# UI_BUTTON_LED.net
KiCad netlist of a schematic drawn in Altium Designer
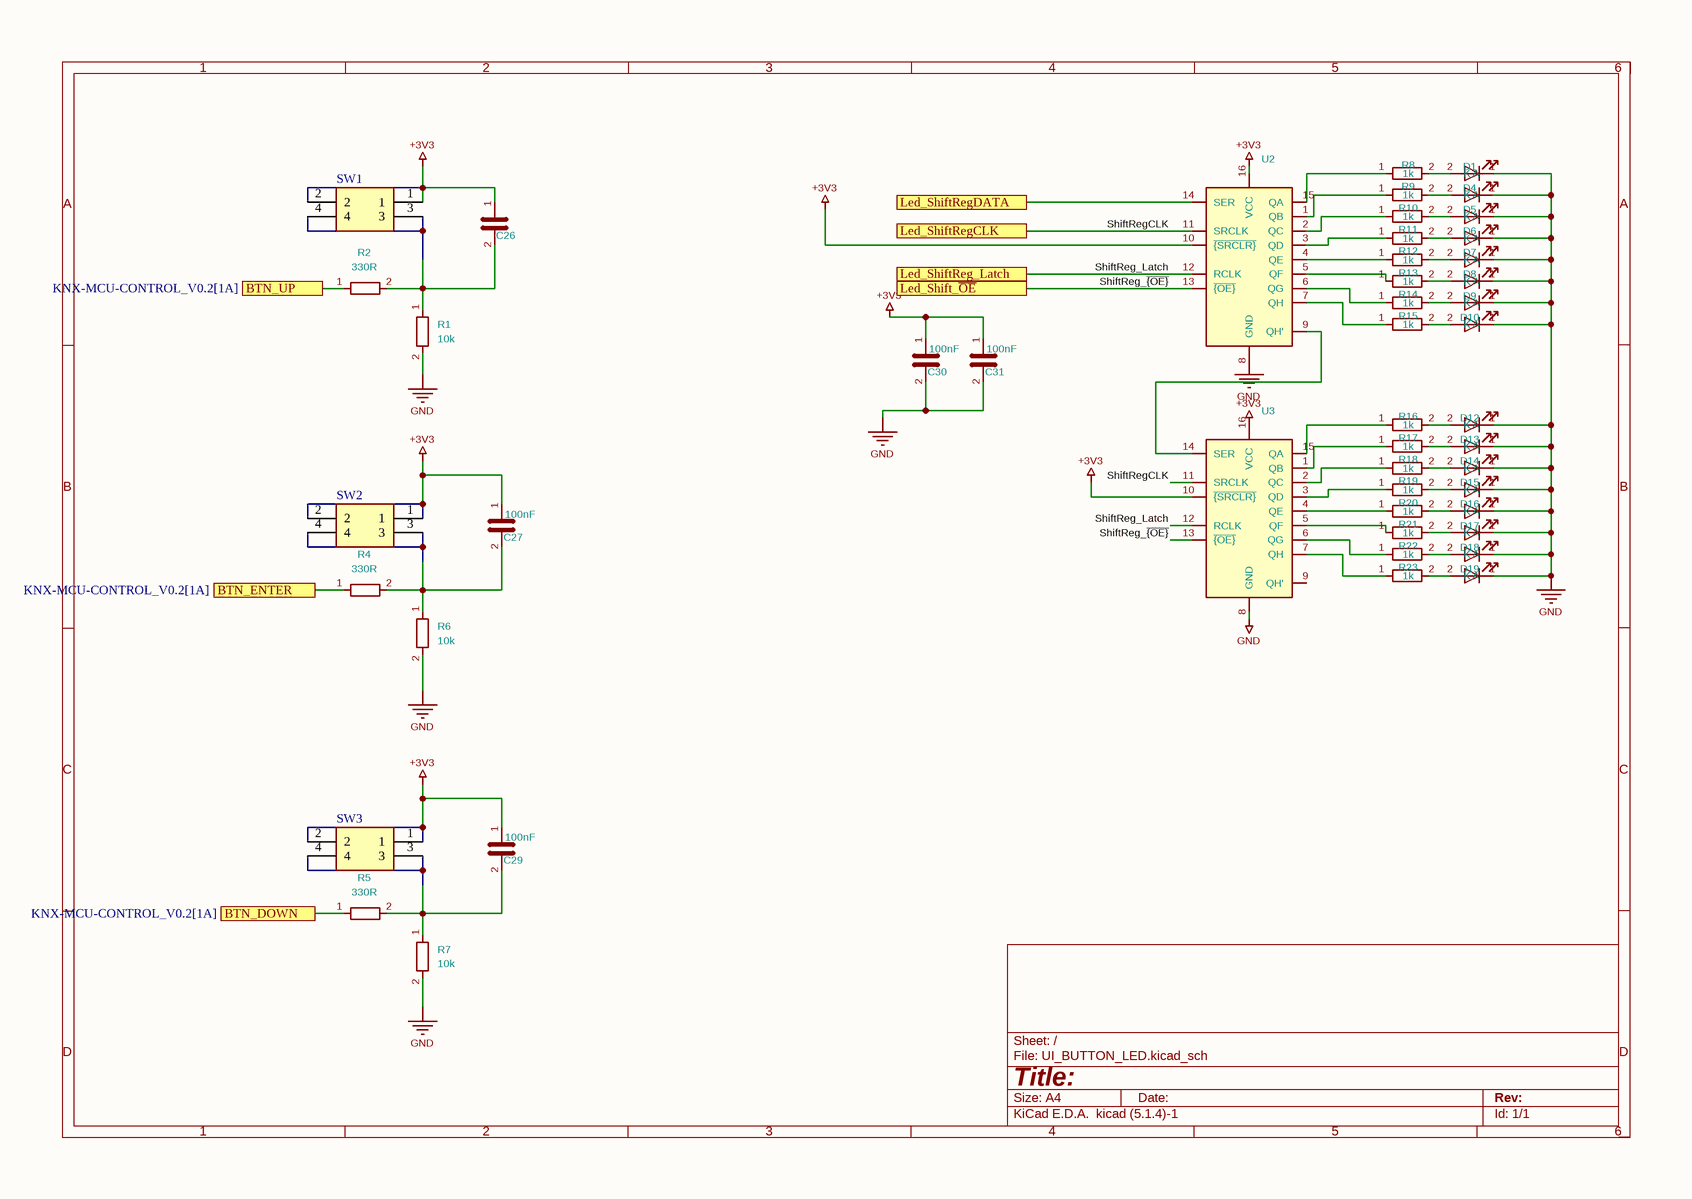
[diagram p0: UI_BUTTON_LED.SchDoc]

(export (version "E")
  (design (tool "Eeschema 10.0.6"))
  (components
    (comp (ref "C26")
      (value "100nF")
      (footprint "C_0603_1608Metric")
      (fields
        (field (name "MANUFACTURER PART NUMBER") "CC0603KRX7R9BB104")
        (field (name "MANUFACTURER") "YAGEO")
      )
      (libsource (lib "*") (part "C_3"))
    )
    (comp (ref "C27")
      (value "100nF")
      (footprint "C_0603_1608Metric")
      (fields
        (field (name "MANUFACTURER PART NUMBER") "CC0603KRX7R9BB104")
        (field (name "MANUFACTURER") "YAGEO")
      )
      (libsource (lib "*") (part "C_3"))
    )
    (comp (ref "C29")
      (value "100nF")
      (footprint "C_0603_1608Metric")
      (fields
        (field (name "MANUFACTURER PART NUMBER") "CC0603KRX7R9BB104")
        (field (name "MANUFACTURER") "YAGEO")
      )
      (libsource (lib "*") (part "C_3"))
    )
    (comp (ref "C30")
      (value "100nF")
      (footprint "C_0603_1608Metric")
      (fields
        (field (name "MANUFACTURER PART NUMBER") "CC0603KRX7R9BB104")
        (field (name "MANUFACTURER") "YAGEO")
      )
      (libsource (lib "*") (part "C_1"))
    )
    (comp (ref "C31")
      (value "100nF")
      (footprint "C_0603_1608Metric")
      (fields
        (field (name "MANUFACTURER PART NUMBER") "CC0603KRX7R9BB104")
        (field (name "MANUFACTURER") "YAGEO")
      )
      (libsource (lib "*") (part "C_1"))
    )
    (comp (ref "D1")
      (value "LED")
      (footprint "LED_0603_1608Metric")
      (fields
        (field (name "MANUFACTURER") "LITEON")
        (field (name "MANUFACTURER PART NUMBER") "LTST-C190KFKT-5A")
      )
      (libsource (lib "Device") (part "LED"))
    )
    (comp (ref "D4")
      (value "LED")
      (footprint "LED_0603_1608Metric")
      (fields
        (field (name "MANUFACTURER") "LITEON")
        (field (name "MANUFACTURER PART NUMBER") "LTST-C190KFKT-5A")
      )
      (libsource (lib "Device") (part "LED"))
    )
    (comp (ref "D5")
      (value "LED")
      (footprint "LED_0603_1608Metric")
      (fields
        (field (name "MANUFACTURER") "LITEON")
        (field (name "MANUFACTURER PART NUMBER") "LTST-C190KFKT-5A")
      )
      (libsource (lib "Device") (part "LED"))
    )
    (comp (ref "D6")
      (value "LED")
      (footprint "LED_0603_1608Metric")
      (fields
        (field (name "MANUFACTURER") "LITEON")
        (field (name "MANUFACTURER PART NUMBER") "LTST-C190KFKT-5A")
      )
      (libsource (lib "Device") (part "LED"))
    )
    (comp (ref "D7")
      (value "LED")
      (footprint "LED_0603_1608Metric")
      (fields
        (field (name "MANUFACTURER") "LITEON")
        (field (name "MANUFACTURER PART NUMBER") "LTST-C190KFKT-5A")
      )
      (libsource (lib "Device") (part "LED"))
    )
    (comp (ref "D8")
      (value "LED")
      (footprint "LED_0603_1608Metric")
      (fields
        (field (name "MANUFACTURER") "LITEON")
        (field (name "MANUFACTURER PART NUMBER") "LTST-C190KFKT-5A")
      )
      (libsource (lib "Device") (part "LED"))
    )
    (comp (ref "D9")
      (value "LED")
      (footprint "LED_0603_1608Metric")
      (fields
        (field (name "MANUFACTURER") "LITEON")
        (field (name "MANUFACTURER PART NUMBER") "LTST-C190KFKT-5A")
      )
      (libsource (lib "Device") (part "LED"))
    )
    (comp (ref "D10")
      (value "LED")
      (footprint "LED_0603_1608Metric")
      (fields
        (field (name "MANUFACTURER") "LITEON")
        (field (name "MANUFACTURER PART NUMBER") "LTST-C190KFKT-5A")
      )
      (libsource (lib "Device") (part "LED"))
    )
    (comp (ref "D12")
      (value "LED")
      (footprint "LED_0603_1608Metric")
      (fields
        (field (name "MANUFACTURER") "LITEON")
        (field (name "MANUFACTURER PART NUMBER") "LTST-C190KFKT-5A")
      )
      (libsource (lib "Device") (part "LED"))
    )
    (comp (ref "D13")
      (value "LED")
      (footprint "LED_0603_1608Metric")
      (fields
        (field (name "MANUFACTURER") "LITEON")
        (field (name "MANUFACTURER PART NUMBER") "LTST-C190KFKT-5A")
      )
      (libsource (lib "Device") (part "LED"))
    )
    (comp (ref "D14")
      (value "LED")
      (footprint "LED_0603_1608Metric")
      (fields
        (field (name "MANUFACTURER") "LITEON")
        (field (name "MANUFACTURER PART NUMBER") "LTST-C190KFKT-5A")
      )
      (libsource (lib "Device") (part "LED"))
    )
    (comp (ref "D15")
      (value "LED")
      (footprint "LED_0603_1608Metric")
      (fields
        (field (name "MANUFACTURER") "LITEON")
        (field (name "MANUFACTURER PART NUMBER") "LTST-C190KFKT-5A")
      )
      (libsource (lib "Device") (part "LED"))
    )
    (comp (ref "D16")
      (value "LED")
      (footprint "LED_0603_1608Metric")
      (fields
        (field (name "MANUFACTURER") "LITEON")
        (field (name "MANUFACTURER PART NUMBER") "LTST-C190KFKT-5A")
      )
      (libsource (lib "Device") (part "LED"))
    )
    (comp (ref "D17")
      (value "LED")
      (footprint "LED_0603_1608Metric")
      (fields
        (field (name "MANUFACTURER") "LITEON")
        (field (name "MANUFACTURER PART NUMBER") "LTST-C190KFKT-5A")
      )
      (libsource (lib "Device") (part "LED"))
    )
    (comp (ref "D18")
      (value "LED")
      (footprint "LED_0603_1608Metric")
      (fields
        (field (name "MANUFACTURER") "LITEON")
        (field (name "MANUFACTURER PART NUMBER") "LTST-C190KFKT-5A")
      )
      (libsource (lib "Device") (part "LED"))
    )
    (comp (ref "D19")
      (value "LED")
      (footprint "LED_0603_1608Metric")
      (fields
        (field (name "MANUFACTURER") "LITEON")
        (field (name "MANUFACTURER PART NUMBER") "LTST-C190KFKT-5A")
      )
      (libsource (lib "Device") (part "LED"))
    )
    (comp (ref "R1")
      (value "10k")
      (footprint "R_0603_1608Metric")
      (fields (field (name "MANUFACTURER") "FOJAN") (field (name "MANUFACTURER PART NUMBER") "FRC0603J103TS"))
      (libsource (lib "") (part "R_1"))
    )
    (comp (ref "R2")
      (value "330R")
      (footprint "R_0603_1608Metric")
      (fields
        (field (name "MANUFACTURER") "FOJAN")
        (field (name "MANUFACTURER PART NUMBER") "FRC0603J331 TS")
      )
      (libsource (lib "Device") (part "R"))
    )
    (comp (ref "R4")
      (value "330R")
      (footprint "R_0603_1608Metric")
      (fields
        (field (name "MANUFACTURER") "FOJAN")
        (field (name "MANUFACTURER PART NUMBER") "FRC0603J331 TS")
      )
      (libsource (lib "Device") (part "R"))
    )
    (comp (ref "R5")
      (value "330R")
      (footprint "R_0603_1608Metric")
      (fields
        (field (name "MANUFACTURER") "FOJAN")
        (field (name "MANUFACTURER PART NUMBER") "FRC0603J331 TS")
      )
      (libsource (lib "Device") (part "R"))
    )
    (comp (ref "R6")
      (value "10k")
      (footprint "R_0603_1608Metric")
      (fields (field (name "MANUFACTURER") "FOJAN") (field (name "MANUFACTURER PART NUMBER") "FRC0603J103TS"))
      (libsource (lib "") (part "R_1"))
    )
    (comp (ref "R7")
      (value "10k")
      (footprint "R_0603_1608Metric")
      (fields (field (name "MANUFACTURER") "FOJAN") (field (name "MANUFACTURER PART NUMBER") "FRC0603J103TS"))
      (libsource (lib "") (part "R_1"))
    )
    (comp (ref "R8")
      (value "1k")
      (footprint "R_0603_1608Metric")
      (fields
        (field (name "MANUFACTURER") "YAGEO")
        (field (name "MANUFACTURER PART NUMBER") "RC0603JR-071KL")
      )
      (libsource (lib "Device") (part "R"))
    )
    (comp (ref "R9")
      (value "1k")
      (footprint "R_0603_1608Metric")
      (fields
        (field (name "MANUFACTURER") "YAGEO")
        (field (name "MANUFACTURER PART NUMBER") "RC0603JR-071KL")
      )
      (libsource (lib "Device") (part "R"))
    )
    (comp (ref "R10")
      (value "1k")
      (footprint "R_0603_1608Metric")
      (fields
        (field (name "MANUFACTURER") "YAGEO")
        (field (name "MANUFACTURER PART NUMBER") "RC0603JR-071KL")
      )
      (libsource (lib "Device") (part "R"))
    )
    (comp (ref "R11")
      (value "1k")
      (footprint "R_0603_1608Metric")
      (fields
        (field (name "MANUFACTURER") "YAGEO")
        (field (name "MANUFACTURER PART NUMBER") "RC0603JR-071KL")
      )
      (libsource (lib "Device") (part "R"))
    )
    (comp (ref "R12")
      (value "1k")
      (footprint "R_0603_1608Metric")
      (fields
        (field (name "MANUFACTURER") "YAGEO")
        (field (name "MANUFACTURER PART NUMBER") "RC0603JR-071KL")
      )
      (libsource (lib "Device") (part "R"))
    )
    (comp (ref "R13")
      (value "1k")
      (footprint "R_0603_1608Metric")
      (fields
        (field (name "MANUFACTURER") "YAGEO")
        (field (name "MANUFACTURER PART NUMBER") "RC0603JR-071KL")
      )
      (libsource (lib "Device") (part "R"))
    )
    (comp (ref "R14")
      (value "1k")
      (footprint "R_0603_1608Metric")
      (fields
        (field (name "MANUFACTURER") "YAGEO")
        (field (name "MANUFACTURER PART NUMBER") "RC0603JR-071KL")
      )
      (libsource (lib "Device") (part "R"))
    )
    (comp (ref "R15")
      (value "1k")
      (footprint "R_0603_1608Metric")
      (fields
        (field (name "MANUFACTURER") "YAGEO")
        (field (name "MANUFACTURER PART NUMBER") "RC0603JR-071KL")
      )
      (libsource (lib "Device") (part "R"))
    )
    (comp (ref "R16")
      (value "1k")
      (footprint "R_0603_1608Metric")
      (fields
        (field (name "MANUFACTURER") "YAGEO")
        (field (name "MANUFACTURER PART NUMBER") "RC0603JR-071KL")
      )
      (libsource (lib "Device") (part "R"))
    )
    (comp (ref "R17")
      (value "1k")
      (footprint "R_0603_1608Metric")
      (fields
        (field (name "MANUFACTURER") "YAGEO")
        (field (name "MANUFACTURER PART NUMBER") "RC0603JR-071KL")
      )
      (libsource (lib "Device") (part "R"))
    )
    (comp (ref "R18")
      (value "1k")
      (footprint "R_0603_1608Metric")
      (fields
        (field (name "MANUFACTURER") "YAGEO")
        (field (name "MANUFACTURER PART NUMBER") "RC0603JR-071KL")
      )
      (libsource (lib "Device") (part "R"))
    )
    (comp (ref "R19")
      (value "1k")
      (footprint "R_0603_1608Metric")
      (fields
        (field (name "MANUFACTURER") "YAGEO")
        (field (name "MANUFACTURER PART NUMBER") "RC0603JR-071KL")
      )
      (libsource (lib "Device") (part "R"))
    )
    (comp (ref "R20")
      (value "1k")
      (footprint "R_0603_1608Metric")
      (fields
        (field (name "MANUFACTURER") "YAGEO")
        (field (name "MANUFACTURER PART NUMBER") "RC0603JR-071KL")
      )
      (libsource (lib "Device") (part "R"))
    )
    (comp (ref "R21")
      (value "1k")
      (footprint "R_0603_1608Metric")
      (fields
        (field (name "MANUFACTURER") "YAGEO")
        (field (name "MANUFACTURER PART NUMBER") "RC0603JR-071KL")
      )
      (libsource (lib "Device") (part "R"))
    )
    (comp (ref "R22")
      (value "1k")
      (footprint "R_0603_1608Metric")
      (fields
        (field (name "MANUFACTURER") "YAGEO")
        (field (name "MANUFACTURER PART NUMBER") "RC0603JR-071KL")
      )
      (libsource (lib "Device") (part "R"))
    )
    (comp (ref "R23")
      (value "1k")
      (footprint "R_0603_1608Metric")
      (fields
        (field (name "MANUFACTURER") "YAGEO")
        (field (name "MANUFACTURER PART NUMBER") "RC0603JR-071KL")
      )
      (libsource (lib "Device") (part "R"))
    )
    (comp (ref "SW1")
      (value "TSA06141-225B532CA-3C00")
      (footprint "SamacSys:TL1105")
      (description "Through Hole-4P,8.2x7.6mm")
      (fields (field (name "MANUFACTURER") "Khon"))
      (libsource (lib "*") (part "TL1105BF160Q"))
    )
    (comp (ref "SW2")
      (value "TSA06141-225B532CA-3C00")
      (footprint "SamacSys:TL1105")
      (description "Through Hole-4P,8.2x7.6mm")
      (fields (field (name "MANUFACTURER") "Khon"))
      (libsource (lib "*") (part "TL1105BF160Q"))
    )
    (comp (ref "SW3")
      (value "TSA06141-225B532CA-3C00")
      (footprint "SamacSys:TL1105")
      (description "Through Hole-4P,8.2x7.6mm")
      (fields (field (name "MANUFACTURER") "Khon"))
      (libsource (lib "*") (part "TL1105BF160Q"))
    )
    (comp (ref "U2")
      (value "74HC595PW,118")
      (footprint "TSSOP-16_4.4x5mm_P0.65mm")
      (fields (field (name "MANUFACTURER") "Nexperia"))
      (libsource (lib "74xx") (part "74HC595"))
    )
    (comp (ref "U3")
      (value "74HC595PW,118")
      (footprint "TSSOP-16_4.4x5mm_P0.65mm")
      (fields (field (name "MANUFACTURER") "Nexperia"))
      (libsource (lib "74xx") (part "74HC595"))
    )
  )
  (nets
    (net (code "1") (name "+3V3") (class "Default")
      (node (ref "C26") (pin "1") (pinfunction "1_1") (pintype "passive"))
      (node (ref "C27") (pin "1") (pinfunction "1_1") (pintype "passive"))
      (node (ref "C29") (pin "1") (pinfunction "1_1") (pintype "passive"))
      (node (ref "C30") (pin "1") (pinfunction "1_1") (pintype "passive"))
      (node (ref "C31") (pin "1") (pinfunction "1_1") (pintype "passive"))
      (node (ref "SW1") (pin "1") (pinfunction "1_1") (pintype "passive"))
      (node (ref "SW1") (pin "2") (pinfunction "2_2") (pintype "passive"))
      (node (ref "SW2") (pin "1") (pinfunction "1_1") (pintype "passive"))
      (node (ref "SW2") (pin "2") (pinfunction "2_2") (pintype "passive"))
      (node (ref "SW3") (pin "1") (pinfunction "1_1") (pintype "passive"))
      (node (ref "SW3") (pin "2") (pinfunction "2_2") (pintype "passive"))
      (node (ref "U2") (pin "10") (pinfunction "~{{SRCLR}}_10") (pintype "passive"))
      (node (ref "U2") (pin "16") (pinfunction "VCC_16") (pintype "passive"))
      (node (ref "U3") (pin "10") (pinfunction "~{{SRCLR}}_10") (pintype "passive"))
      (node (ref "U3") (pin "16") (pinfunction "VCC_16") (pintype "passive"))
    )
    (net (code "2") (name "/BTN_DOWN") (class "Default")
      (node (ref "R5") (pin "1") (pinfunction "1_1") (pintype "passive"))
    )
    (net (code "3") (name "/BTN_ENTER") (class "Default")
      (node (ref "R4") (pin "1") (pinfunction "1_1") (pintype "passive"))
    )
    (net (code "4") (name "/BTN_UP") (class "Default")
      (node (ref "R2") (pin "1") (pinfunction "1_1") (pintype "passive"))
    )
    (net (code "5") (name "/Led_ShiftRegDATA") (class "Default")
      (node (ref "U2") (pin "14") (pinfunction "SER_14") (pintype "passive"))
    )
    (net (code "6") (name "/ShiftRegCLK") (class "Default")
      (node (ref "U2") (pin "11") (pinfunction "SRCLK_11") (pintype "passive"))
      (node (ref "U3") (pin "11") (pinfunction "SRCLK_11") (pintype "passive"))
    )
    (net (code "7") (name "/ShiftReg_Latch") (class "Default")
      (node (ref "U2") (pin "12") (pinfunction "RCLK_12") (pintype "passive"))
      (node (ref "U3") (pin "12") (pinfunction "RCLK_12") (pintype "passive"))
    )
    (net (code "8") (name "/ShiftReg_~{{OE}}") (class "Default")
      (node (ref "U2") (pin "13") (pinfunction "~{{OE}}_13") (pintype "passive"))
      (node (ref "U3") (pin "13") (pinfunction "~{{OE}}_13") (pintype "passive"))
    )
    (net (code "9") (name "GND") (class "Default")
      (node (ref "C30") (pin "2") (pinfunction "2_2") (pintype "passive"))
      (node (ref "C31") (pin "2") (pinfunction "2_2") (pintype "passive"))
      (node (ref "D1") (pin "1") (pinfunction "K_1") (pintype "passive"))
      (node (ref "D10") (pin "1") (pinfunction "K_1") (pintype "passive"))
      (node (ref "D12") (pin "1") (pinfunction "K_1") (pintype "passive"))
      (node (ref "D13") (pin "1") (pinfunction "K_1") (pintype "passive"))
      (node (ref "D14") (pin "1") (pinfunction "K_1") (pintype "passive"))
      (node (ref "D15") (pin "1") (pinfunction "K_1") (pintype "passive"))
      (node (ref "D16") (pin "1") (pinfunction "K_1") (pintype "passive"))
      (node (ref "D17") (pin "1") (pinfunction "K_1") (pintype "passive"))
      (node (ref "D18") (pin "1") (pinfunction "K_1") (pintype "passive"))
      (node (ref "D19") (pin "1") (pinfunction "K_1") (pintype "passive"))
      (node (ref "D4") (pin "1") (pinfunction "K_1") (pintype "passive"))
      (node (ref "D5") (pin "1") (pinfunction "K_1") (pintype "passive"))
      (node (ref "D6") (pin "1") (pinfunction "K_1") (pintype "passive"))
      (node (ref "D7") (pin "1") (pinfunction "K_1") (pintype "passive"))
      (node (ref "D8") (pin "1") (pinfunction "K_1") (pintype "passive"))
      (node (ref "D9") (pin "1") (pinfunction "K_1") (pintype "passive"))
      (node (ref "R1") (pin "2") (pinfunction "2_2") (pintype "passive"))
      (node (ref "R6") (pin "2") (pinfunction "2_2") (pintype "passive"))
      (node (ref "R7") (pin "2") (pinfunction "2_2") (pintype "passive"))
      (node (ref "U2") (pin "8") (pinfunction "GND_8") (pintype "passive"))
      (node (ref "U3") (pin "8") (pinfunction "GND_8") (pintype "passive"))
    )
    (net (code "10") (name "Net-(C26-Pad2)") (class "Default")
      (node (ref "C26") (pin "2") (pinfunction "2_2") (pintype "passive"))
      (node (ref "R1") (pin "1") (pinfunction "1_1") (pintype "passive"))
      (node (ref "R2") (pin "2") (pinfunction "2_2") (pintype "passive"))
      (node (ref "SW1") (pin "3") (pinfunction "3_3") (pintype "passive"))
      (node (ref "SW1") (pin "4") (pinfunction "4_4") (pintype "passive"))
    )
    (net (code "11") (name "Net-(C27-Pad2)") (class "Default")
      (node (ref "C27") (pin "2") (pinfunction "2_2") (pintype "passive"))
      (node (ref "R4") (pin "2") (pinfunction "2_2") (pintype "passive"))
      (node (ref "R6") (pin "1") (pinfunction "1_1") (pintype "passive"))
      (node (ref "SW2") (pin "3") (pinfunction "3_3") (pintype "passive"))
      (node (ref "SW2") (pin "4") (pinfunction "4_4") (pintype "passive"))
    )
    (net (code "12") (name "Net-(C29-Pad2)") (class "Default")
      (node (ref "C29") (pin "2") (pinfunction "2_2") (pintype "passive"))
      (node (ref "R5") (pin "2") (pinfunction "2_2") (pintype "passive"))
      (node (ref "R7") (pin "1") (pinfunction "1_1") (pintype "passive"))
      (node (ref "SW3") (pin "3") (pinfunction "3_3") (pintype "passive"))
      (node (ref "SW3") (pin "4") (pinfunction "4_4") (pintype "passive"))
    )
    (net (code "13") (name "Net-(D1-A)") (class "Default")
      (node (ref "D1") (pin "2") (pinfunction "A_2") (pintype "passive"))
      (node (ref "R8") (pin "2") (pinfunction "2_2") (pintype "passive"))
    )
    (net (code "14") (name "Net-(D4-A)") (class "Default")
      (node (ref "D4") (pin "2") (pinfunction "A_2") (pintype "passive"))
      (node (ref "R9") (pin "2") (pinfunction "2_2") (pintype "passive"))
    )
    (net (code "15") (name "Net-(D5-A)") (class "Default")
      (node (ref "D5") (pin "2") (pinfunction "A_2") (pintype "passive"))
      (node (ref "R10") (pin "2") (pinfunction "2_2") (pintype "passive"))
    )
    (net (code "16") (name "Net-(D6-A)") (class "Default")
      (node (ref "D6") (pin "2") (pinfunction "A_2") (pintype "passive"))
      (node (ref "R11") (pin "2") (pinfunction "2_2") (pintype "passive"))
    )
    (net (code "17") (name "Net-(D7-A)") (class "Default")
      (node (ref "D7") (pin "2") (pinfunction "A_2") (pintype "passive"))
      (node (ref "R12") (pin "2") (pinfunction "2_2") (pintype "passive"))
    )
    (net (code "18") (name "Net-(D8-A)") (class "Default")
      (node (ref "D8") (pin "2") (pinfunction "A_2") (pintype "passive"))
      (node (ref "R13") (pin "2") (pinfunction "2_2") (pintype "passive"))
    )
    (net (code "19") (name "Net-(D9-A)") (class "Default")
      (node (ref "D9") (pin "2") (pinfunction "A_2") (pintype "passive"))
      (node (ref "R14") (pin "2") (pinfunction "2_2") (pintype "passive"))
    )
    (net (code "20") (name "Net-(D10-A)") (class "Default")
      (node (ref "D10") (pin "2") (pinfunction "A_2") (pintype "passive"))
      (node (ref "R15") (pin "2") (pinfunction "2_2") (pintype "passive"))
    )
    (net (code "21") (name "Net-(D12-A)") (class "Default")
      (node (ref "D12") (pin "2") (pinfunction "A_2") (pintype "passive"))
      (node (ref "R16") (pin "2") (pinfunction "2_2") (pintype "passive"))
    )
    (net (code "22") (name "Net-(D13-A)") (class "Default")
      (node (ref "D13") (pin "2") (pinfunction "A_2") (pintype "passive"))
      (node (ref "R17") (pin "2") (pinfunction "2_2") (pintype "passive"))
    )
    (net (code "23") (name "Net-(D14-A)") (class "Default")
      (node (ref "D14") (pin "2") (pinfunction "A_2") (pintype "passive"))
      (node (ref "R18") (pin "2") (pinfunction "2_2") (pintype "passive"))
    )
    (net (code "24") (name "Net-(D15-A)") (class "Default")
      (node (ref "D15") (pin "2") (pinfunction "A_2") (pintype "passive"))
      (node (ref "R19") (pin "2") (pinfunction "2_2") (pintype "passive"))
    )
    (net (code "25") (name "Net-(D16-A)") (class "Default")
      (node (ref "D16") (pin "2") (pinfunction "A_2") (pintype "passive"))
      (node (ref "R20") (pin "2") (pinfunction "2_2") (pintype "passive"))
    )
    (net (code "26") (name "Net-(D17-A)") (class "Default")
      (node (ref "D17") (pin "2") (pinfunction "A_2") (pintype "passive"))
      (node (ref "R21") (pin "2") (pinfunction "2_2") (pintype "passive"))
    )
    (net (code "27") (name "Net-(D18-A)") (class "Default")
      (node (ref "D18") (pin "2") (pinfunction "A_2") (pintype "passive"))
      (node (ref "R22") (pin "2") (pinfunction "2_2") (pintype "passive"))
    )
    (net (code "28") (name "Net-(D19-A)") (class "Default")
      (node (ref "D19") (pin "2") (pinfunction "A_2") (pintype "passive"))
      (node (ref "R23") (pin "2") (pinfunction "2_2") (pintype "passive"))
    )
    (net (code "29") (name "Net-(U2-QA)") (class "Default")
      (node (ref "R8") (pin "1") (pinfunction "1_1") (pintype "passive"))
      (node (ref "U2") (pin "15") (pinfunction "QA_15") (pintype "passive"))
    )
    (net (code "30") (name "Net-(U2-QB)") (class "Default")
      (node (ref "R9") (pin "1") (pinfunction "1_1") (pintype "passive"))
      (node (ref "U2") (pin "1") (pinfunction "QB_1") (pintype "passive"))
    )
    (net (code "31") (name "Net-(U2-QC)") (class "Default")
      (node (ref "R10") (pin "1") (pinfunction "1_1") (pintype "passive"))
      (node (ref "U2") (pin "2") (pinfunction "QC_2") (pintype "passive"))
    )
    (net (code "32") (name "Net-(U2-QD)") (class "Default")
      (node (ref "R11") (pin "1") (pinfunction "1_1") (pintype "passive"))
      (node (ref "U2") (pin "3") (pinfunction "QD_3") (pintype "passive"))
    )
    (net (code "33") (name "Net-(U2-QE)") (class "Default")
      (node (ref "R12") (pin "1") (pinfunction "1_1") (pintype "passive"))
      (node (ref "U2") (pin "4") (pinfunction "QE_4") (pintype "passive"))
    )
    (net (code "34") (name "Net-(U2-QF)") (class "Default")
      (node (ref "R13") (pin "1") (pinfunction "1_1") (pintype "passive"))
      (node (ref "U2") (pin "5") (pinfunction "QF_5") (pintype "passive"))
    )
    (net (code "35") (name "Net-(U2-QG)") (class "Default")
      (node (ref "R14") (pin "1") (pinfunction "1_1") (pintype "passive"))
      (node (ref "U2") (pin "6") (pinfunction "QG_6") (pintype "passive"))
    )
    (net (code "36") (name "Net-(U2-QH')") (class "Default")
      (node (ref "U2") (pin "9") (pinfunction "QH'_9") (pintype "passive"))
      (node (ref "U3") (pin "14") (pinfunction "SER_14") (pintype "passive"))
    )
    (net (code "37") (name "Net-(U2-QH)") (class "Default")
      (node (ref "R15") (pin "1") (pinfunction "1_1") (pintype "passive"))
      (node (ref "U2") (pin "7") (pinfunction "QH_7") (pintype "passive"))
    )
    (net (code "38") (name "Net-(U3-QA)") (class "Default")
      (node (ref "R16") (pin "1") (pinfunction "1_1") (pintype "passive"))
      (node (ref "U3") (pin "15") (pinfunction "QA_15") (pintype "passive"))
    )
    (net (code "39") (name "Net-(U3-QB)") (class "Default")
      (node (ref "R17") (pin "1") (pinfunction "1_1") (pintype "passive"))
      (node (ref "U3") (pin "1") (pinfunction "QB_1") (pintype "passive"))
    )
    (net (code "40") (name "Net-(U3-QC)") (class "Default")
      (node (ref "R18") (pin "1") (pinfunction "1_1") (pintype "passive"))
      (node (ref "U3") (pin "2") (pinfunction "QC_2") (pintype "passive"))
    )
    (net (code "41") (name "Net-(U3-QD)") (class "Default")
      (node (ref "R19") (pin "1") (pinfunction "1_1") (pintype "passive"))
      (node (ref "U3") (pin "3") (pinfunction "QD_3") (pintype "passive"))
    )
    (net (code "42") (name "Net-(U3-QE)") (class "Default")
      (node (ref "R20") (pin "1") (pinfunction "1_1") (pintype "passive"))
      (node (ref "U3") (pin "4") (pinfunction "QE_4") (pintype "passive"))
    )
    (net (code "43") (name "Net-(U3-QF)") (class "Default")
      (node (ref "R21") (pin "1") (pinfunction "1_1") (pintype "passive"))
      (node (ref "U3") (pin "5") (pinfunction "QF_5") (pintype "passive"))
    )
    (net (code "44") (name "Net-(U3-QG)") (class "Default")
      (node (ref "R22") (pin "1") (pinfunction "1_1") (pintype "passive"))
      (node (ref "U3") (pin "6") (pinfunction "QG_6") (pintype "passive"))
    )
    (net (code "45") (name "Net-(U3-QH)") (class "Default")
      (node (ref "R23") (pin "1") (pinfunction "1_1") (pintype "passive"))
      (node (ref "U3") (pin "7") (pinfunction "QH_7") (pintype "passive"))
    )
    (net (code "46") (name "unconnected-(U3-QH'-Pad9)") (class "Default")
      (node (ref "U3") (pin "9") (pinfunction "QH'_9") (pintype "passive"))
    )
  )
)
